# ESP-32-UNICLOCK-VFD.net
KiCad netlist of a schematic drawn in EAGLE
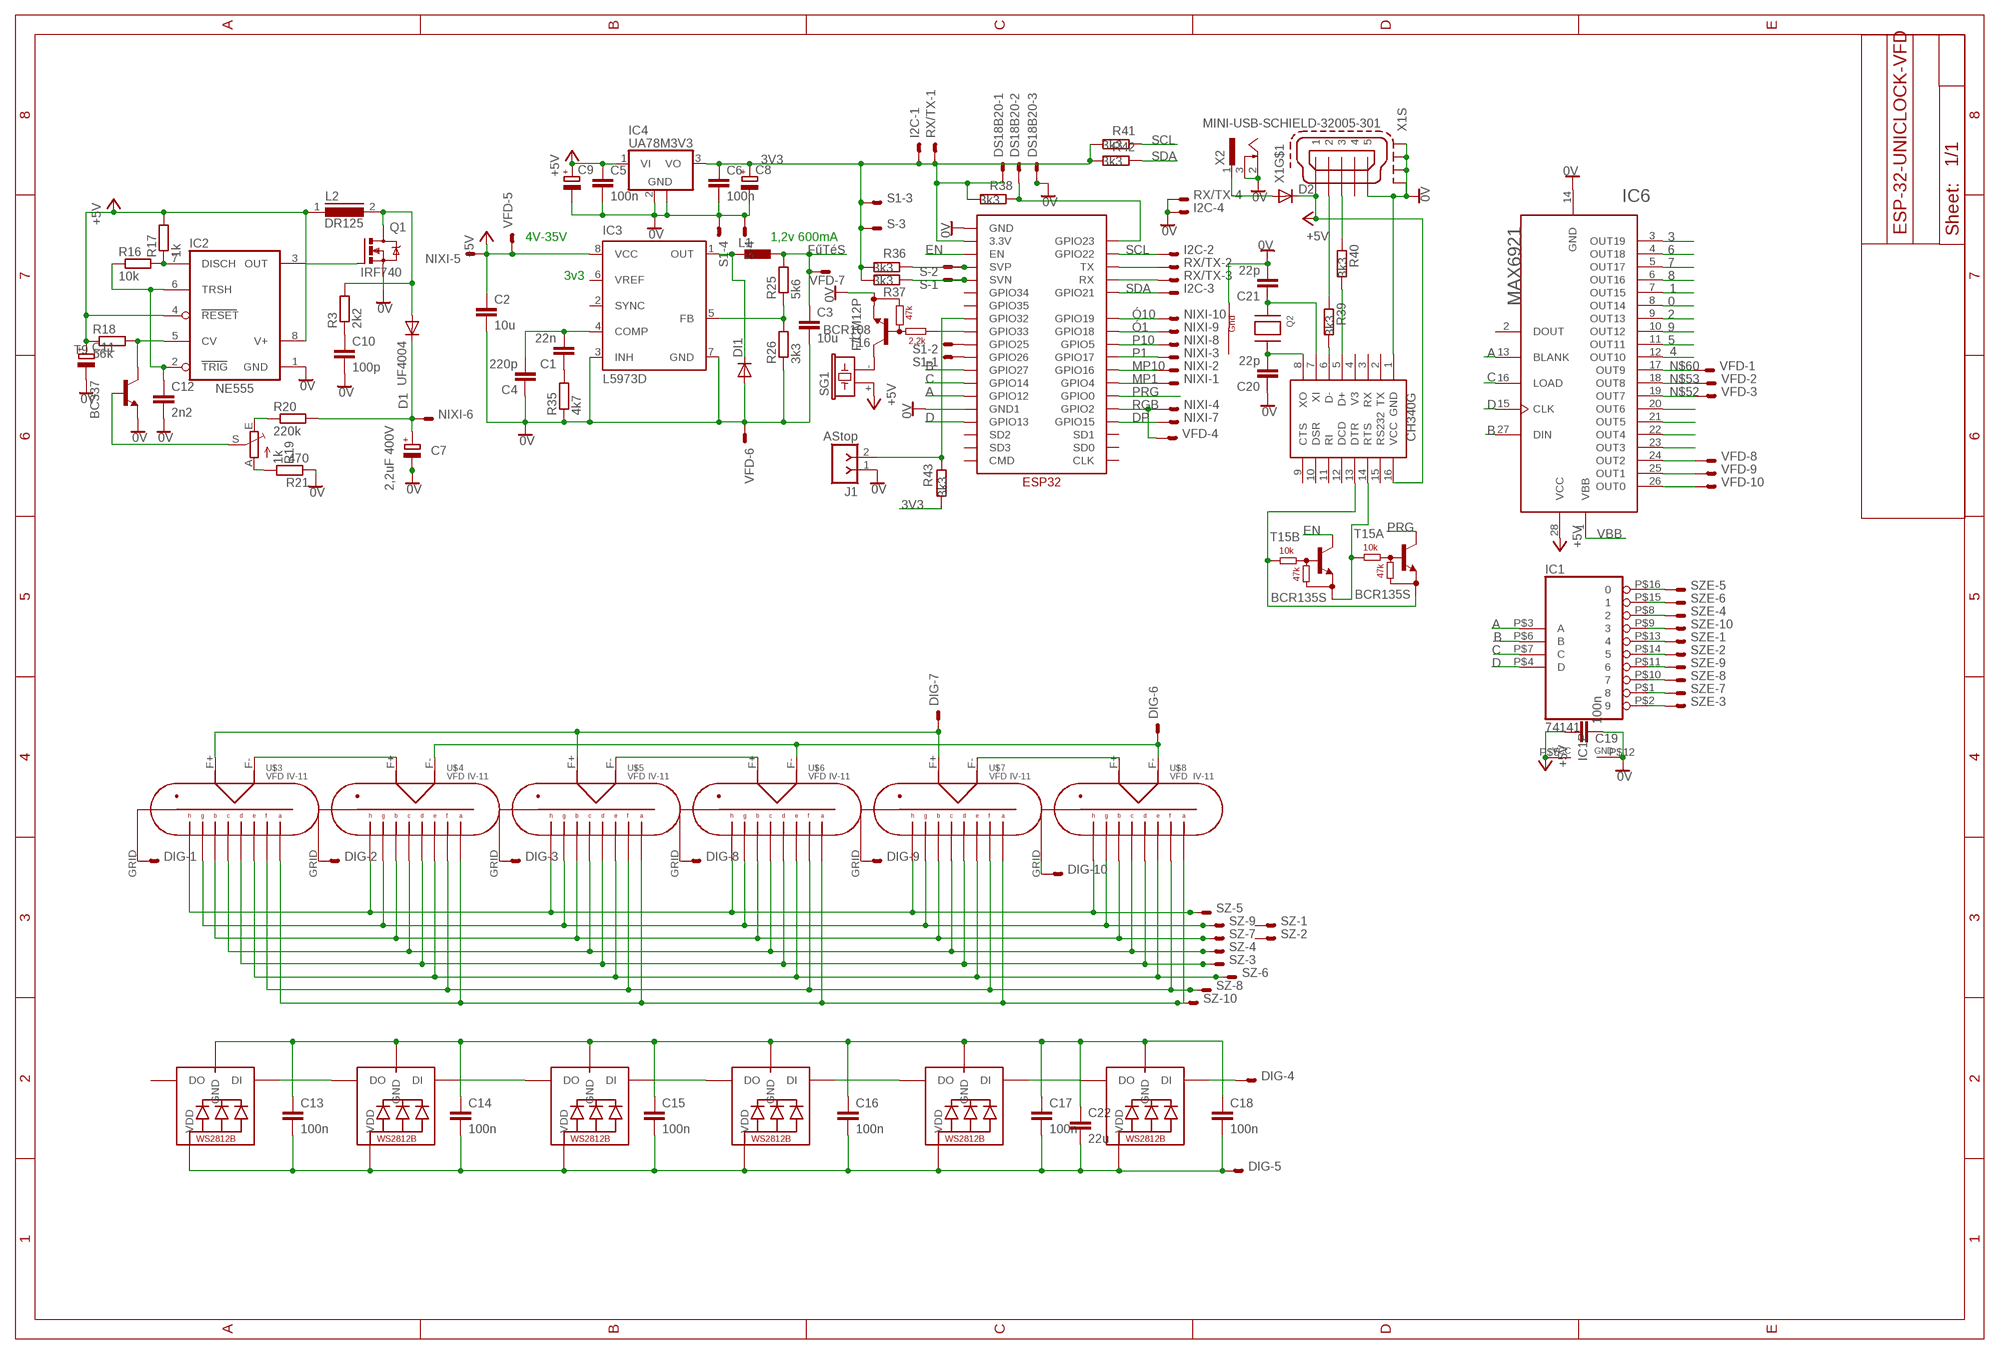
[diagram p0: schematic, sheet 1]

(export (version "E")
  (design (tool "Eeschema 10.0.6"))
  (components
    (comp (ref "C1")
      (value "22n")
      (footprint "eagle-import:0603")
      (libsource (lib "eagle-import") (part "C0603"))
    )
    (comp (ref "C2")
      (value "10u")
      (footprint "eagle-import:1206")
      (libsource (lib "eagle-import") (part "C1206"))
    )
    (comp (ref "C3")
      (value "10u")
      (footprint "eagle-import:1206")
      (libsource (lib "eagle-import") (part "C1206"))
    )
    (comp (ref "C4")
      (value "220p")
      (footprint "eagle-import:0603")
      (libsource (lib "eagle-import") (part "C0603"))
    )
    (comp (ref "C5")
      (value "100n")
      (footprint "eagle-import:0603")
      (libsource (lib "eagle-import") (part "C0603"))
    )
    (comp (ref "C6")
      (value "100n")
      (footprint "eagle-import:0603")
      (libsource (lib "eagle-import") (part "C0603"))
    )
    (comp (ref "C7")
      (value "2,2uF 400V")
      (footprint "eagle-import:E2,5-7")
      (libsource (lib "eagle-import") (part "CPOL-EUE2.5-7"))
    )
    (comp (ref "C8")
      (value "CPOL-EUE2.5-5")
      (footprint "eagle-import:E2,5-5")
      (libsource (lib "eagle-import") (part "CPOL-EUE2.5-5"))
    )
    (comp (ref "C9")
      (value "CPOL-EUE2.5-5")
      (footprint "eagle-import:E2,5-5")
      (libsource (lib "eagle-import") (part "CPOL-EUE2.5-5"))
    )
    (comp (ref "C10")
      (value "100p")
      (footprint "eagle-import:C050-024X044")
      (libsource (lib "eagle-import") (part "C-EU050-024X044"))
    )
    (comp (ref "C11")
      (value "CPOL-EUE2.5-7")
      (footprint "eagle-import:E2,5-7")
      (libsource (lib "eagle-import") (part "CPOL-EUE2.5-7"))
    )
    (comp (ref "C12")
      (value "2n2")
      (footprint "eagle-import:C0603")
      (libsource (lib "eagle-import") (part "C-EUC0603"))
    )
    (comp (ref "C13")
      (value "100n")
      (footprint "eagle-import:C0603")
      (libsource (lib "eagle-import") (part "C-EUC0603"))
    )
    (comp (ref "C14")
      (value "100n")
      (footprint "eagle-import:C0603")
      (libsource (lib "eagle-import") (part "C-EUC0603"))
    )
    (comp (ref "C15")
      (value "100n")
      (footprint "eagle-import:C0603")
      (libsource (lib "eagle-import") (part "C-EUC0603"))
    )
    (comp (ref "C16")
      (value "100n")
      (footprint "eagle-import:C0603")
      (libsource (lib "eagle-import") (part "C-EUC0603"))
    )
    (comp (ref "C17")
      (value "100n")
      (footprint "eagle-import:C0603")
      (libsource (lib "eagle-import") (part "C-EUC0603"))
    )
    (comp (ref "C18")
      (value "100n")
      (footprint "eagle-import:C0603")
      (libsource (lib "eagle-import") (part "C-EUC0603"))
    )
    (comp (ref "C19")
      (value "100n")
      (footprint "eagle-import:0603")
      (libsource (lib "eagle-import") (part "C0603"))
    )
    (comp (ref "C20")
      (value "22p")
      (footprint "eagle-import:0603")
      (libsource (lib "eagle-import") (part "C0603"))
    )
    (comp (ref "C21")
      (value "22p")
      (footprint "eagle-import:0603")
      (libsource (lib "eagle-import") (part "C0603"))
    )
    (comp (ref "C22")
      (value "22u")
      (footprint "eagle-import:C1206K")
      (libsource (lib "eagle-import") (part "C-EUC1206K"))
    )
    (comp (ref "D1")
      (value "UF4004")
      (footprint "eagle-import:DO35-10")
      (libsource (lib "eagle-import") (part "BA221"))
    )
    (comp (ref "D2")
      (value "DIODE-SOD123")
      (footprint "eagle-import:SOD123")
      (libsource (lib "eagle-import") (part "DIODE-SOD123"))
    )
    (comp (ref "DI1")
      (value "DDI214")
      (footprint "eagle-import:DI-214")
      (libsource (lib "eagle-import") (part "DDI214"))
    )
    (comp (ref "DIG")
      (value "DIG")
      (footprint "eagle-import:PAD10")
      (libsource (lib "eagle-import") (part "PAD10"))
    )
    (comp (ref "DS18B20")
      (value "PAD3")
      (footprint "eagle-import:PAD3")
      (libsource (lib "eagle-import") (part "PAD3"))
    )
    (comp (ref "I2C")
      (value "PAD4")
      (footprint "eagle-import:PAD4")
      (libsource (lib "eagle-import") (part "PAD4"))
    )
    (comp (ref "IC1")
      (value "74141")
      (footprint "eagle-import:DIL16SMD")
      (libsource (lib "eagle-import") (part "74141"))
    )
    (comp (ref "IC2")
      (value "NE555")
      (footprint "eagle-import:DIL08")
      (fields (field (name "MF") "MAXIM") (field (name "MPN") "ICM7555IPA+"))
      (libsource (lib "eagle-import") (part "ICM7555"))
    )
    (comp (ref "IC3")
      (value "L5973D")
      (footprint "eagle-import:HSOP8")
      (fields (field (name "MF") "STMICROELECTRONICS"))
      (libsource (lib "eagle-import") (part "L5973D"))
    )
    (comp (ref "IC4")
      (value "UA78M3V3")
      (footprint "eagle-import:SOT223")
      (libsource (lib "eagle-import") (part "UA78MDCY05"))
    )
    (comp (ref "IC6")
      (value "MAX6921")
      (footprint "eagle-import:SO-28W")
      (libsource (lib "eagle-import") (part "MAX6921SOIC28W"))
    )
    (comp (ref "J1")
      (value "AStop")
      (footprint "eagle-import:SIP-100-02-32")
      (libsource (lib "eagle-import") (part "F-1X02-SIP-100-32"))
    )
    (comp (ref "L1")
      (value "LDR73A")
      (footprint "eagle-import:DR73A")
      (libsource (lib "eagle-import") (part "LDR73A"))
    )
    (comp (ref "L2")
      (value "DR125")
      (footprint "eagle-import:DR125")
      (libsource (lib "eagle-import") (part "DR125"))
    )
    (comp (ref "LED1")
      (value "WS2812B_5050N")
      (footprint "eagle-import:WS2812B-NARROW")
      (libsource (lib "eagle-import") (part "WS2812B_5050N"))
    )
    (comp (ref "LED2")
      (value "WS2812B_5050N")
      (footprint "eagle-import:WS2812B-NARROW")
      (libsource (lib "eagle-import") (part "WS2812B_5050N"))
    )
    (comp (ref "LED3")
      (value "WS2812B_5050N")
      (footprint "eagle-import:WS2812B-NARROW")
      (libsource (lib "eagle-import") (part "WS2812B_5050N"))
    )
    (comp (ref "LED4")
      (value "WS2812B_5050N")
      (footprint "eagle-import:WS2812B-NARROW")
      (libsource (lib "eagle-import") (part "WS2812B_5050N"))
    )
    (comp (ref "LED5")
      (value "WS2812B_5050N")
      (footprint "eagle-import:WS2812B-NARROW")
      (libsource (lib "eagle-import") (part "WS2812B_5050N"))
    )
    (comp (ref "LED6")
      (value "WS2812B_5050N")
      (footprint "eagle-import:WS2812B-NARROW")
      (libsource (lib "eagle-import") (part "WS2812B_5050N"))
    )
    (comp (ref "NIXI")
      (value "PAD10")
      (footprint "eagle-import:PAD10")
      (libsource (lib "eagle-import") (part "PAD10"))
    )
    (comp (ref "Q1")
      (value "IRF740")
      (footprint "eagle-import:TO220BV")
      (libsource (lib "eagle-import") (part "IRF740"))
    )
    (comp (ref "Q2")
      (value "XTAL-4-3225")
      (footprint "eagle-import:NX3225")
      (libsource (lib "eagle-import") (part "XTAL-4-3225"))
    )
    (comp (ref "R3")
      (value "2k2")
      (footprint "eagle-import:0204_7")
      (libsource (lib "eagle-import") (part "R-EU_0204/7"))
    )
    (comp (ref "R16")
      (value "10k")
      (footprint "eagle-import:R0603")
      (libsource (lib "eagle-import") (part "R-EU_R0603"))
    )
    (comp (ref "R17")
      (value "1k")
      (footprint "eagle-import:R0603")
      (libsource (lib "eagle-import") (part "R-EU_R0603"))
    )
    (comp (ref "R18")
      (value "56k")
      (footprint "eagle-import:R0603")
      (libsource (lib "eagle-import") (part "R-EU_R0603"))
    )
    (comp (ref "R19")
      (value "1k")
      (footprint "eagle-import:CA6H")
      (libsource (lib "eagle-import") (part "TRIM_EU-CA6H"))
    )
    (comp (ref "R20")
      (value "220k")
      (footprint "eagle-import:0204_7")
      (libsource (lib "eagle-import") (part "R-EU_0204/7"))
    )
    (comp (ref "R21")
      (value "470")
      (footprint "eagle-import:0204_7")
      (libsource (lib "eagle-import") (part "R-EU_0204/7"))
    )
    (comp (ref "R25")
      (value "5k6")
      (footprint "eagle-import:0603")
      (libsource (lib "eagle-import") (part "R0603"))
    )
    (comp (ref "R26")
      (value "3k3")
      (footprint "eagle-import:0603")
      (libsource (lib "eagle-import") (part "R0603"))
    )
    (comp (ref "R35")
      (value "4k7")
      (footprint "eagle-import:0603")
      (libsource (lib "eagle-import") (part "R0603"))
    )
    (comp (ref "R36")
      (value "3k3")
      (footprint "eagle-import:0603")
      (libsource (lib "eagle-import") (part "R0603"))
    )
    (comp (ref "R37")
      (value "3k3")
      (footprint "eagle-import:0603")
      (libsource (lib "eagle-import") (part "R0603"))
    )
    (comp (ref "R38")
      (value "3k3")
      (footprint "eagle-import:0603")
      (libsource (lib "eagle-import") (part "R0603"))
    )
    (comp (ref "R39")
      (value "3k3")
      (footprint "eagle-import:0603")
      (libsource (lib "eagle-import") (part "R0603"))
    )
    (comp (ref "R40")
      (value "3k3")
      (footprint "eagle-import:0603")
      (libsource (lib "eagle-import") (part "R0603"))
    )
    (comp (ref "R41")
      (value "3k3")
      (footprint "eagle-import:0603")
      (libsource (lib "eagle-import") (part "R0603"))
    )
    (comp (ref "R42")
      (value "3k3")
      (footprint "eagle-import:0603")
      (libsource (lib "eagle-import") (part "R0603"))
    )
    (comp (ref "R43")
      (value "3k3")
      (footprint "eagle-import:0603")
      (libsource (lib "eagle-import") (part "R0603"))
    )
    (comp (ref "RX/TX")
      (value "PAD4")
      (footprint "eagle-import:PAD4")
      (libsource (lib "eagle-import") (part "PAD4"))
    )
    (comp (ref "S")
      (value "PAD4")
      (footprint "eagle-import:PAD4")
      (libsource (lib "eagle-import") (part "PAD4"))
    )
    (comp (ref "S1")
      (value "PAD4")
      (footprint "eagle-import:PAD4")
      (libsource (lib "eagle-import") (part "PAD4"))
    )
    (comp (ref "SG1")
      (value "F/CM12P")
      (footprint "eagle-import:F_CM12P")
      (libsource (lib "eagle-import") (part "F/CM12P"))
    )
    (comp (ref "SZ")
      (value "PAD10")
      (footprint "eagle-import:PAD10")
      (libsource (lib "eagle-import") (part "PAD10"))
    )
    (comp (ref "SZE")
      (value "PAD10")
      (footprint "eagle-import:PAD10")
      (libsource (lib "eagle-import") (part "PAD10"))
    )
    (comp (ref "T9")
      (value "BC337")
      (footprint "eagle-import:TO92-CBE")
      (libsource (lib "eagle-import") (part "-NPN-TO92-CBEBC237"))
    )
    (comp (ref "T15")
      (value "BCR135S")
      (footprint "eagle-import:SOT363_INFINEON")
      (libsource (lib "eagle-import") (part "BCR135S"))
    )
    (comp (ref "T16")
      (value "BCR108")
      (footprint "eagle-import:SOT23-BEC")
      (libsource (lib "eagle-import") (part "BCR108"))
    )
    (comp (ref "U$1")
      (value "CH340G")
      (footprint "eagle-import:SOIC16")
      (libsource (lib "eagle-import") (part "CH340G"))
    )
    (comp (ref "U$2")
      (value "ESP32-2X18")
      (footprint "eagle-import:ESP322X18")
      (libsource (lib "eagle-import") (part "ESP32-2X18"))
    )
    (comp (ref "U$3")
      (value "VFD IV-11")
      (footprint "eagle-import:VFD-IV_11-ZOLI")
      (libsource (lib "eagle-import") (part "VFD-IV-11-ZOLI"))
    )
    (comp (ref "U$4")
      (value "VFD IV-11")
      (footprint "eagle-import:VFD-IV_11-ZOLI")
      (libsource (lib "eagle-import") (part "VFD-IV-11-ZOLI"))
    )
    (comp (ref "U$5")
      (value "VFD IV-11")
      (footprint "eagle-import:VFD-IV_11-ZOLI")
      (libsource (lib "eagle-import") (part "VFD-IV-11-ZOLI"))
    )
    (comp (ref "U$6")
      (value "VFD IV-11")
      (footprint "eagle-import:VFD-IV_11-ZOLI")
      (libsource (lib "eagle-import") (part "VFD-IV-11-ZOLI"))
    )
    (comp (ref "U$7")
      (value "VFD IV-11")
      (footprint "eagle-import:VFD-IV_11-ZOLI")
      (libsource (lib "eagle-import") (part "VFD-IV-11-ZOLI"))
    )
    (comp (ref "U$8")
      (value "VFD IV-11")
      (footprint "eagle-import:VFD-IV_11-ZOLI")
      (libsource (lib "eagle-import") (part "VFD-IV-11-ZOLI"))
    )
    (comp (ref "VFD")
      (value "PAD10")
      (footprint "eagle-import:PAD10")
      (libsource (lib "eagle-import") (part "PAD10"))
    )
    (comp (ref "X1")
      (value "MINI-USB-SCHIELD-32005-301")
      (footprint "eagle-import:32005-301")
      (libsource (lib "eagle-import") (part "MINI-USB-SCHIELD-32005-301"))
    )
    (comp (ref "X2")
      (value "733989-5")
      (footprint "eagle-import:733989-5")
      (libsource (lib "eagle-import") (part "73398?9-5"))
    )
  )
  (nets
    (net (code "1") (name "+5V") (class "Default")
      (node (ref "C11") (pin "+") (pinfunction "+_+") (pintype "passive"))
      (node (ref "C19") (pin "1") (pinfunction "1_1") (pintype "passive"))
      (node (ref "C2") (pin "1") (pinfunction "1_1") (pintype "passive"))
      (node (ref "C5") (pin "1") (pinfunction "1_1") (pintype "passive"))
      (node (ref "C9") (pin "+") (pinfunction "+_+") (pintype "passive"))
      (node (ref "D2") (pin "C") (pinfunction "C_C") (pintype "passive"))
      (node (ref "IC1") (pin "P$5") (pinfunction "VCC_P$5") (pintype "power_in"))
      (node (ref "IC2") (pin "4") (pinfunction "RESET_4") (pintype "input"))
      (node (ref "IC2") (pin "8") (pinfunction "V+_8") (pintype "power_in"))
      (node (ref "IC3") (pin "8") (pinfunction "VCC_8") (pintype "input"))
      (node (ref "IC4") (pin "1") (pinfunction "VI_1") (pintype "input"))
      (node (ref "IC6") (pin "28") (pinfunction "VCC_28") (pintype "power_in"))
      (node (ref "L2") (pin "1") (pinfunction "1_1") (pintype "passive"))
      (node (ref "NIXI") (pin "P$5") (pinfunction "S_P$5") (pintype "passive"))
      (node (ref "R17") (pin "2") (pinfunction "2_2") (pintype "passive"))
      (node (ref "R18") (pin "1") (pinfunction "1_1") (pintype "passive"))
      (node (ref "SG1") (pin "+") (pinfunction "1_+") (pintype "passive"))
      (node (ref "U$1") (pin "16") (pinfunction "VCC_16") (pintype "bidirectional"))
      (node (ref "VFD") (pin "P$5") (pinfunction "S_P$5") (pintype "passive"))
      (node (ref "X1") (pin "1") (pinfunction "1_1") (pintype "passive"))
    )
    (net (code "2") (name "/0") (class "Default")
      (node (ref "IC1") (pin "P$16") (pinfunction "0_P$16") (pintype "open_collector"))
      (node (ref "IC6") (pin "8") (pinfunction "OUT14_8") (pintype "output"))
      (node (ref "SZE") (pin "P$5") (pinfunction "S_P$5") (pintype "passive"))
    )
    (net (code "3") (name "/1") (class "Default")
      (node (ref "IC1") (pin "P$15") (pinfunction "1_P$15") (pintype "open_collector"))
      (node (ref "IC6") (pin "7") (pinfunction "OUT15_7") (pintype "output"))
      (node (ref "SZE") (pin "P$6") (pinfunction "S_P$6") (pintype "passive"))
    )
    (net (code "4") (name "/2") (class "Default")
      (node (ref "IC1") (pin "P$8") (pinfunction "2_P$8") (pintype "open_collector"))
      (node (ref "IC6") (pin "9") (pinfunction "OUT13_9") (pintype "output"))
      (node (ref "SZE") (pin "P$4") (pinfunction "S_P$4") (pintype "passive"))
    )
    (net (code "5") (name "/3") (class "Default")
      (node (ref "IC1") (pin "P$9") (pinfunction "3_P$9") (pintype "open_collector"))
      (node (ref "IC6") (pin "3") (pinfunction "OUT19_3") (pintype "output"))
      (node (ref "SZE") (pin "P$10") (pinfunction "S_P$10") (pintype "passive"))
    )
    (net (code "6") (name "/3V3") (class "Default")
      (node (ref "C6") (pin "1") (pinfunction "1_1") (pintype "passive"))
      (node (ref "C8") (pin "+") (pinfunction "+_+") (pintype "passive"))
      (node (ref "DS18B20") (pin "P$1") (pinfunction "S_P$1") (pintype "passive"))
      (node (ref "I2C") (pin "P$1") (pinfunction "S_P$1") (pintype "passive"))
      (node (ref "IC4") (pin "3") (pinfunction "VO_3") (pintype "passive"))
      (node (ref "R36") (pin "2") (pinfunction "2_2") (pintype "passive"))
      (node (ref "R37") (pin "2") (pinfunction "2_2") (pintype "passive"))
      (node (ref "R38") (pin "2") (pinfunction "2_2") (pintype "passive"))
      (node (ref "R41") (pin "2") (pinfunction "2_2") (pintype "passive"))
      (node (ref "R42") (pin "2") (pinfunction "2_2") (pintype "passive"))
      (node (ref "R43") (pin "2") (pinfunction "2_2") (pintype "passive"))
      (node (ref "RX/TX") (pin "P$1") (pinfunction "S_P$1") (pintype "passive"))
      (node (ref "S") (pin "P$3") (pinfunction "S_P$3") (pintype "passive"))
      (node (ref "S1") (pin "P$3") (pinfunction "S_P$3") (pintype "passive"))
      (node (ref "U$2") (pin "P$20") (pinfunction "3.3V_P$20") (pintype "bidirectional"))
    )
    (net (code "7") (name "/4") (class "Default")
      (node (ref "IC1") (pin "P$13") (pinfunction "4_P$13") (pintype "open_collector"))
      (node (ref "IC6") (pin "12") (pinfunction "OUT10_12") (pintype "output"))
      (node (ref "SZE") (pin "P$1") (pinfunction "S_P$1") (pintype "passive"))
    )
    (net (code "8") (name "/5") (class "Default")
      (node (ref "IC1") (pin "P$14") (pinfunction "5_P$14") (pintype "open_collector"))
      (node (ref "IC6") (pin "11") (pinfunction "OUT11_11") (pintype "output"))
      (node (ref "SZE") (pin "P$2") (pinfunction "S_P$2") (pintype "passive"))
    )
    (net (code "9") (name "/6") (class "Default")
      (node (ref "IC1") (pin "P$11") (pinfunction "6_P$11") (pintype "open_collector"))
      (node (ref "IC6") (pin "4") (pinfunction "OUT18_4") (pintype "output"))
      (node (ref "SZE") (pin "P$9") (pinfunction "S_P$9") (pintype "passive"))
    )
    (net (code "10") (name "/7") (class "Default")
      (node (ref "IC1") (pin "P$10") (pinfunction "7_P$10") (pintype "open_collector"))
      (node (ref "IC6") (pin "5") (pinfunction "OUT17_5") (pintype "output"))
      (node (ref "SZE") (pin "P$8") (pinfunction "S_P$8") (pintype "passive"))
    )
    (net (code "11") (name "/8") (class "Default")
      (node (ref "IC1") (pin "P$1") (pinfunction "8_P$1") (pintype "open_collector"))
      (node (ref "IC6") (pin "6") (pinfunction "OUT16_6") (pintype "output"))
      (node (ref "SZE") (pin "P$7") (pinfunction "S_P$7") (pintype "passive"))
    )
    (net (code "12") (name "/9") (class "Default")
      (node (ref "IC1") (pin "P$2") (pinfunction "9_P$2") (pintype "open_collector"))
      (node (ref "IC6") (pin "10") (pinfunction "OUT12_10") (pintype "output"))
      (node (ref "SZE") (pin "P$3") (pinfunction "S_P$3") (pintype "passive"))
    )
    (net (code "13") (name "/A") (class "Default")
      (node (ref "IC1") (pin "P$3") (pinfunction "A_P$3") (pintype "input"))
      (node (ref "IC6") (pin "13") (pinfunction "BLANK_13") (pintype "input"))
      (node (ref "U$2") (pin "P$12") (pinfunction "GPIO12_P$12") (pintype "bidirectional"))
    )
    (net (code "14") (name "/B") (class "Default")
      (node (ref "IC1") (pin "P$6") (pinfunction "B_P$6") (pintype "input"))
      (node (ref "IC6") (pin "27") (pinfunction "DIN_27") (pintype "input"))
      (node (ref "U$2") (pin "P$10") (pinfunction "GPIO27_P$10") (pintype "bidirectional"))
    )
    (net (code "15") (name "/C") (class "Default")
      (node (ref "IC1") (pin "P$7") (pinfunction "C_P$7") (pintype "input"))
      (node (ref "IC6") (pin "16") (pinfunction "LOAD_16") (pintype "input"))
      (node (ref "U$2") (pin "P$9") (pinfunction "GPIO14_P$9") (pintype "bidirectional"))
    )
    (net (code "16") (name "/D") (class "Default")
      (node (ref "IC1") (pin "P$4") (pinfunction "D_P$4") (pintype "input"))
      (node (ref "IC6") (pin "15") (pinfunction "CLK_15") (pintype "input"))
      (node (ref "U$2") (pin "P$11") (pinfunction "GPIO13_P$11") (pintype "bidirectional"))
    )
    (net (code "17") (name "/DP") (class "Default")
      (node (ref "NIXI") (pin "P$7") (pinfunction "S_P$7") (pintype "passive"))
      (node (ref "U$2") (pin "P$35") (pinfunction "GPIO15_P$35") (pintype "bidirectional"))
    )
    (net (code "18") (name "/EN") (class "Default")
      (node (ref "T15") (pin "3") (pinfunction "C_3") (pintype "passive"))
      (node (ref "U$2") (pin "P$21") (pinfunction "EN_P$21") (pintype "bidirectional"))
    )
    (net (code "19") (name "/FűTéS") (class "Default")
      (node (ref "C3") (pin "1") (pinfunction "1_1") (pintype "passive"))
      (node (ref "L1") (pin "2") (pinfunction "2_2") (pintype "passive"))
      (node (ref "R25") (pin "2") (pinfunction "2_2") (pintype "passive"))
      (node (ref "VFD") (pin "P$7") (pinfunction "S_P$7") (pintype "passive"))
    )
    (net (code "20") (name "/G2") (class "Default")
      (node (ref "Q2") (pin "2") (pinfunction "G2_2") (pintype "power_in"))
    )
    (net (code "21") (name "/GND") (class "Default")
      (node (ref "C13") (pin "1") (pinfunction "1_1") (pintype "passive"))
      (node (ref "C14") (pin "1") (pinfunction "1_1") (pintype "passive"))
      (node (ref "C15") (pin "1") (pinfunction "1_1") (pintype "passive"))
      (node (ref "C16") (pin "1") (pinfunction "1_1") (pintype "passive"))
      (node (ref "C17") (pin "1") (pinfunction "1_1") (pintype "passive"))
      (node (ref "C18") (pin "1") (pinfunction "1_1") (pintype "passive"))
      (node (ref "C22") (pin "1") (pinfunction "1_1") (pintype "passive"))
      (node (ref "DIG") (pin "P$6") (pinfunction "S_P$6") (pintype "passive"))
      (node (ref "LED1") (pin "3-GND") (pinfunction "GND_3-GND") (pintype "power_in"))
      (node (ref "LED2") (pin "3-GND") (pinfunction "GND_3-GND") (pintype "power_in"))
      (node (ref "LED3") (pin "3-GND") (pinfunction "GND_3-GND") (pintype "power_in"))
      (node (ref "LED4") (pin "3-GND") (pinfunction "GND_3-GND") (pintype "power_in"))
      (node (ref "LED5") (pin "3-GND") (pinfunction "GND_3-GND") (pintype "power_in"))
      (node (ref "LED6") (pin "3-GND") (pinfunction "GND_3-GND") (pintype "power_in"))
      (node (ref "U$4") (pin "F-") (pinfunction "F-_F-") (pintype "passive"))
      (node (ref "U$6") (pin "F-") (pinfunction "F-_F-") (pintype "passive"))
      (node (ref "U$8") (pin "F-") (pinfunction "F-_F-") (pintype "passive"))
    )
    (net (code "22") (name "/MP1") (class "Default")
      (node (ref "NIXI") (pin "P$1") (pinfunction "S_P$1") (pintype "passive"))
      (node (ref "U$2") (pin "P$34") (pinfunction "GPIO4_P$34") (pintype "bidirectional"))
    )
    (net (code "23") (name "/MP10") (class "Default")
      (node (ref "NIXI") (pin "P$2") (pinfunction "S_P$2") (pintype "passive"))
      (node (ref "U$2") (pin "P$31") (pinfunction "GPIO16_P$31") (pintype "bidirectional"))
    )
    (net (code "24") (name "/N$52") (class "Default")
      (node (ref "IC6") (pin "19") (pinfunction "OUT7_19") (pintype "output"))
      (node (ref "VFD") (pin "P$3") (pinfunction "S_P$3") (pintype "passive"))
    )
    (net (code "25") (name "/N$53") (class "Default")
      (node (ref "IC6") (pin "18") (pinfunction "OUT8_18") (pintype "output"))
      (node (ref "VFD") (pin "P$2") (pinfunction "S_P$2") (pintype "passive"))
    )
    (net (code "26") (name "/N$60") (class "Default")
      (node (ref "IC6") (pin "17") (pinfunction "OUT9_17") (pintype "output"))
      (node (ref "VFD") (pin "P$1") (pinfunction "S_P$1") (pintype "passive"))
    )
    (net (code "27") (name "/P1") (class "Default")
      (node (ref "NIXI") (pin "P$3") (pinfunction "S_P$3") (pintype "passive"))
      (node (ref "U$2") (pin "P$32") (pinfunction "GPIO17_P$32") (pintype "bidirectional"))
    )
    (net (code "28") (name "/P10") (class "Default")
      (node (ref "NIXI") (pin "P$8") (pinfunction "S_P$8") (pintype "passive"))
      (node (ref "U$2") (pin "P$29") (pinfunction "GPIO5_P$29") (pintype "bidirectional"))
    )
    (net (code "29") (name "/PRG") (class "Default")
      (node (ref "T15") (pin "6") (pinfunction "C_6") (pintype "passive"))
      (node (ref "U$2") (pin "P$33") (pinfunction "GPIO0_P$33") (pintype "bidirectional"))
    )
    (net (code "30") (name "/RGB") (class "Default")
      (node (ref "NIXI") (pin "P$4") (pinfunction "S_P$4") (pintype "passive"))
      (node (ref "U$2") (pin "P$36") (pinfunction "GPIO2_P$36") (pintype "bidirectional"))
      (node (ref "VFD") (pin "P$4") (pinfunction "S_P$4") (pintype "passive"))
    )
    (net (code "31") (name "/SCL") (class "Default")
      (node (ref "I2C") (pin "P$2") (pinfunction "S_P$2") (pintype "passive"))
      (node (ref "R41") (pin "1") (pinfunction "1_1") (pintype "passive"))
      (node (ref "U$2") (pin "P$25") (pinfunction "GPIO22_P$25") (pintype "bidirectional"))
    )
    (net (code "32") (name "/SDA") (class "Default")
      (node (ref "I2C") (pin "P$3") (pinfunction "S_P$3") (pintype "passive"))
      (node (ref "R42") (pin "1") (pinfunction "1_1") (pintype "passive"))
      (node (ref "U$2") (pin "P$28") (pinfunction "GPIO21_P$28") (pintype "bidirectional"))
    )
    (net (code "33") (name "/VBB") (class "Default")
      (node (ref "C7") (pin "+") (pinfunction "+_+") (pintype "passive"))
      (node (ref "D1") (pin "C") (pinfunction "C_C") (pintype "passive"))
      (node (ref "IC6") (pin "1") (pinfunction "VBB_1") (pintype "power_in"))
      (node (ref "NIXI") (pin "P$6") (pinfunction "S_P$6") (pintype "passive"))
      (node (ref "R20") (pin "2") (pinfunction "2_2") (pintype "passive"))
    )
    (net (code "34") (name "/Ó1") (class "Default")
      (node (ref "NIXI") (pin "P$9") (pinfunction "S_P$9") (pintype "passive"))
      (node (ref "U$2") (pin "P$30") (pinfunction "GPIO18_P$30") (pintype "bidirectional"))
    )
    (net (code "35") (name "/Ó10") (class "Default")
      (node (ref "NIXI") (pin "P$10") (pinfunction "S_P$10") (pintype "passive"))
      (node (ref "U$2") (pin "P$27") (pinfunction "GPIO19_P$27") (pintype "bidirectional"))
    )
    (net (code "36") (name "0V") (class "Default")
      (node (ref "C10") (pin "2") (pinfunction "2_2") (pintype "passive"))
      (node (ref "C11") (pin "-") (pinfunction "-_-") (pintype "passive"))
      (node (ref "C12") (pin "2") (pinfunction "2_2") (pintype "passive"))
      (node (ref "C19") (pin "2") (pinfunction "2_2") (pintype "passive"))
      (node (ref "C2") (pin "2") (pinfunction "2_2") (pintype "passive"))
      (node (ref "C20") (pin "1") (pinfunction "1_1") (pintype "passive"))
      (node (ref "C21") (pin "2") (pinfunction "2_2") (pintype "passive"))
      (node (ref "C3") (pin "2") (pinfunction "2_2") (pintype "passive"))
      (node (ref "C4") (pin "1") (pinfunction "1_1") (pintype "passive"))
      (node (ref "C5") (pin "2") (pinfunction "2_2") (pintype "passive"))
      (node (ref "C6") (pin "2") (pinfunction "2_2") (pintype "passive"))
      (node (ref "C7") (pin "-") (pinfunction "-_-") (pintype "passive"))
      (node (ref "C8") (pin "-") (pinfunction "-_-") (pintype "passive"))
      (node (ref "C9") (pin "-") (pinfunction "-_-") (pintype "passive"))
      (node (ref "DI1") (pin "A") (pinfunction "A_A") (pintype "passive"))
      (node (ref "DS18B20") (pin "P$3") (pinfunction "S_P$3") (pintype "passive"))
      (node (ref "I2C") (pin "P$4") (pinfunction "S_P$4") (pintype "passive"))
      (node (ref "IC1") (pin "P$12") (pinfunction "GND_P$12") (pintype "power_in"))
      (node (ref "IC2") (pin "1") (pinfunction "GND_1") (pintype "power_in"))
      (node (ref "IC3") (pin "3") (pinfunction "INH_3") (pintype "input"))
      (node (ref "IC3") (pin "7") (pinfunction "GND_7") (pintype "power_in"))
      (node (ref "IC4") (pin "2") (pinfunction "GND_2") (pintype "passive"))
      (node (ref "IC4") (pin "4") (pinfunction "GND_4") (pintype "passive"))
      (node (ref "IC6") (pin "14") (pinfunction "GND_14") (pintype "power_in"))
      (node (ref "J1") (pin "1") (pinfunction "1_1") (pintype "passive"))
      (node (ref "Q1") (pin "S") (pinfunction "S_S") (pintype "passive"))
      (node (ref "Q2") (pin "4") (pinfunction "G1_4") (pintype "power_in"))
      (node (ref "R21") (pin "1") (pinfunction "1_1") (pintype "passive"))
      (node (ref "R26") (pin "1") (pinfunction "1_1") (pintype "passive"))
      (node (ref "R35") (pin "1") (pinfunction "1_1") (pintype "passive"))
      (node (ref "RX/TX") (pin "P$4") (pinfunction "S_P$4") (pintype "passive"))
      (node (ref "S") (pin "P$4") (pinfunction "S_P$4") (pintype "passive"))
      (node (ref "S1") (pin "P$4") (pinfunction "S_P$4") (pintype "passive"))
      (node (ref "T16") (pin "E") (pinfunction "E_E") (pintype "passive"))
      (node (ref "T9") (pin "E") (pinfunction "E_E") (pintype "passive"))
      (node (ref "U$1") (pin "1") (pinfunction "GND_1") (pintype "bidirectional"))
      (node (ref "U$2") (pin "P$19") (pinfunction "GND_P$19") (pintype "bidirectional"))
      (node (ref "U$2") (pin "P$26") (pinfunction "GND1_P$26") (pintype "bidirectional"))
      (node (ref "VFD") (pin "P$6") (pinfunction "S_P$6") (pintype "passive"))
      (node (ref "X1") (pin "5") (pinfunction "5_5") (pintype "passive"))
      (node (ref "X1") (pin "M1") (pinfunction "S1_M1") (pintype "passive"))
      (node (ref "X1") (pin "M2") (pinfunction "S2_M2") (pintype "passive"))
      (node (ref "X1") (pin "M3") (pinfunction "S3_M3") (pintype "passive"))
      (node (ref "X1") (pin "M4") (pinfunction "S4_M4") (pintype "passive"))
      (node (ref "X2") (pin "2") (pinfunction "2_2") (pintype "passive"))
      (node (ref "X2") (pin "3") (pinfunction "3_3") (pintype "passive"))
    )
    (net (code "37") (name "Net-(C1-Pad1)") (class "Default")
      (node (ref "C1") (pin "1") (pinfunction "1_1") (pintype "passive"))
      (node (ref "R35") (pin "2") (pinfunction "2_2") (pintype "passive"))
    )
    (net (code "38") (name "Net-(C10-Pad1)") (class "Default")
      (node (ref "C10") (pin "1") (pinfunction "1_1") (pintype "passive"))
      (node (ref "R3") (pin "1") (pinfunction "1_1") (pintype "passive"))
    )
    (net (code "39") (name "Net-(D1-PadA)") (class "Default")
      (node (ref "D1") (pin "A") (pinfunction "A_A") (pintype "passive"))
      (node (ref "L2") (pin "2") (pinfunction "2_2") (pintype "passive"))
      (node (ref "Q1") (pin "D") (pinfunction "D_D") (pintype "passive"))
      (node (ref "R3") (pin "2") (pinfunction "2_2") (pintype "passive"))
    )
    (net (code "40") (name "Net-(D2-PadA)") (class "Default")
      (node (ref "D2") (pin "A") (pinfunction "A_A") (pintype "passive"))
      (node (ref "X2") (pin "1") (pinfunction "1_1") (pintype "passive"))
    )
    (net (code "41") (name "Net-(DI1-C)") (class "Default")
      (node (ref "DI1") (pin "K") (pinfunction "C_K") (pintype "passive"))
      (node (ref "IC3") (pin "1") (pinfunction "OUT_1") (pintype "output"))
      (node (ref "L1") (pin "1") (pinfunction "1_1") (pintype "passive"))
    )
    (net (code "42") (name "Net-(DIGA-S)") (class "Default")
      (node (ref "DIG") (pin "P$1") (pinfunction "S_P$1") (pintype "passive"))
      (node (ref "U$3") (pin "GRID") (pinfunction "GRID_GRID") (pintype "passive"))
    )
    (net (code "43") (name "Net-(DIGB-S)") (class "Default")
      (node (ref "DIG") (pin "P$10") (pinfunction "S_P$10") (pintype "passive"))
      (node (ref "U$8") (pin "GRID") (pinfunction "GRID_GRID") (pintype "passive"))
    )
    (net (code "44") (name "Net-(DIGC-S)") (class "Default")
      (node (ref "DIG") (pin "P$2") (pinfunction "S_P$2") (pintype "passive"))
      (node (ref "U$4") (pin "GRID") (pinfunction "GRID_GRID") (pintype "passive"))
    )
    (net (code "45") (name "Net-(DIGD-S)") (class "Default")
      (node (ref "DIG") (pin "P$3") (pinfunction "S_P$3") (pintype "passive"))
      (node (ref "U$5") (pin "GRID") (pinfunction "GRID_GRID") (pintype "passive"))
    )
    (net (code "46") (name "Net-(DIGE-S)") (class "Default")
      (node (ref "DIG") (pin "P$4") (pinfunction "S_P$4") (pintype "passive"))
      (node (ref "LED1") (pin "4-DIN") (pinfunction "DI_4-DIN") (pintype "input"))
    )
    (net (code "47") (name "Net-(DIGF-S)") (class "Default")
      (node (ref "C13") (pin "2") (pinfunction "2_2") (pintype "passive"))
      (node (ref "C14") (pin "2") (pinfunction "2_2") (pintype "passive"))
      (node (ref "C15") (pin "2") (pinfunction "2_2") (pintype "passive"))
      (node (ref "C16") (pin "2") (pinfunction "2_2") (pintype "passive"))
      (node (ref "C17") (pin "2") (pinfunction "2_2") (pintype "passive"))
      (node (ref "C18") (pin "2") (pinfunction "2_2") (pintype "passive"))
      (node (ref "C22") (pin "2") (pinfunction "2_2") (pintype "passive"))
      (node (ref "DIG") (pin "P$5") (pinfunction "S_P$5") (pintype "passive"))
      (node (ref "LED1") (pin "1-VDD") (pinfunction "VDD_1-VDD") (pintype "power_in"))
      (node (ref "LED2") (pin "1-VDD") (pinfunction "VDD_1-VDD") (pintype "power_in"))
      (node (ref "LED3") (pin "1-VDD") (pinfunction "VDD_1-VDD") (pintype "power_in"))
      (node (ref "LED4") (pin "1-VDD") (pinfunction "VDD_1-VDD") (pintype "power_in"))
      (node (ref "LED5") (pin "1-VDD") (pinfunction "VDD_1-VDD") (pintype "power_in"))
      (node (ref "LED6") (pin "1-VDD") (pinfunction "VDD_1-VDD") (pintype "power_in"))
    )
    (net (code "48") (name "Net-(DIGH-S)") (class "Default")
      (node (ref "DIG") (pin "P$7") (pinfunction "S_P$7") (pintype "passive"))
      (node (ref "U$3") (pin "F+") (pinfunction "F+_F+") (pintype "passive"))
      (node (ref "U$5") (pin "F+") (pinfunction "F+_F+") (pintype "passive"))
      (node (ref "U$7") (pin "F+") (pinfunction "F+_F+") (pintype "passive"))
    )
    (net (code "49") (name "Net-(DIGI-S)") (class "Default")
      (node (ref "DIG") (pin "P$8") (pinfunction "S_P$8") (pintype "passive"))
      (node (ref "U$6") (pin "GRID") (pinfunction "GRID_GRID") (pintype "passive"))
    )
    (net (code "50") (name "Net-(DIGJ-S)") (class "Default")
      (node (ref "DIG") (pin "P$9") (pinfunction "S_P$9") (pintype "passive"))
      (node (ref "U$7") (pin "GRID") (pinfunction "GRID_GRID") (pintype "passive"))
    )
    (net (code "51") (name "Net-(DS18B20B-S)") (class "Default")
      (node (ref "DS18B20") (pin "P$2") (pinfunction "S_P$2") (pintype "passive"))
      (node (ref "R38") (pin "1") (pinfunction "1_1") (pintype "passive"))
      (node (ref "U$2") (pin "P$23") (pinfunction "GPIO23_P$23") (pintype "bidirectional"))
    )
    (net (code "52") (name "Net-(IC2-CV)") (class "Default")
      (node (ref "IC2") (pin "5") (pinfunction "CV_5") (pintype "passive"))
      (node (ref "R18") (pin "2") (pinfunction "2_2") (pintype "passive"))
      (node (ref "T9") (pin "C") (pinfunction "C_C") (pintype "passive"))
    )
    (net (code "53") (name "Net-(IC2-DISCH)") (class "Default")
      (node (ref "IC2") (pin "7") (pinfunction "DISCH_7") (pintype "input"))
      (node (ref "R16") (pin "2") (pinfunction "2_2") (pintype "passive"))
      (node (ref "R17") (pin "1") (pinfunction "1_1") (pintype "passive"))
    )
    (net (code "54") (name "Net-(IC2-OUT)") (class "Default")
      (node (ref "IC2") (pin "3") (pinfunction "OUT_3") (pintype "output"))
      (node (ref "Q1") (pin "G") (pinfunction "G_G") (pintype "passive"))
    )
    (net (code "55") (name "Net-(IC2-TRIG)") (class "Default")
      (node (ref "C12") (pin "1") (pinfunction "1_1") (pintype "passive"))
      (node (ref "IC2") (pin "2") (pinfunction "TRIG_2") (pintype "bidirectional"))
      (node (ref "IC2") (pin "6") (pinfunction "TRSH_6") (pintype "input"))
      (node (ref "R16") (pin "1") (pinfunction "1_1") (pintype "passive"))
    )
    (net (code "56") (name "Net-(IC3B-COMP)") (class "Default")
      (node (ref "C1") (pin "2") (pinfunction "2_2") (pintype "passive"))
      (node (ref "C4") (pin "2") (pinfunction "2_2") (pintype "passive"))
      (node (ref "IC3") (pin "4") (pinfunction "COMP_4") (pintype "passive"))
    )
    (net (code "57") (name "Net-(IC3B-FB)") (class "Default")
      (node (ref "IC3") (pin "5") (pinfunction "FB_5") (pintype "input"))
      (node (ref "R25") (pin "1") (pinfunction "1_1") (pintype "passive"))
      (node (ref "R26") (pin "2") (pinfunction "2_2") (pintype "passive"))
    )
    (net (code "58") (name "Net-(IC6-OUT0)") (class "Default")
      (node (ref "IC6") (pin "26") (pinfunction "OUT0_26") (pintype "output"))
      (node (ref "VFD") (pin "P$10") (pinfunction "S_P$10") (pintype "passive"))
    )
    (net (code "59") (name "Net-(IC6-OUT1)") (class "Default")
      (node (ref "IC6") (pin "25") (pinfunction "OUT1_25") (pintype "output"))
      (node (ref "VFD") (pin "P$9") (pinfunction "S_P$9") (pintype "passive"))
    )
    (net (code "60") (name "Net-(IC6-OUT2)") (class "Default")
      (node (ref "IC6") (pin "24") (pinfunction "OUT2_24") (pintype "output"))
      (node (ref "VFD") (pin "P$8") (pinfunction "S_P$8") (pintype "passive"))
    )
    (net (code "61") (name "Net-(LED1-DO)") (class "Default")
      (node (ref "LED1") (pin "2-DOUT") (pinfunction "DO_2-DOUT") (pintype "output"))
      (node (ref "LED2") (pin "4-DIN") (pinfunction "DI_4-DIN") (pintype "input"))
    )
    (net (code "62") (name "Net-(LED2-DO)") (class "Default")
      (node (ref "LED2") (pin "2-DOUT") (pinfunction "DO_2-DOUT") (pintype "output"))
      (node (ref "LED3") (pin "4-DIN") (pinfunction "DI_4-DIN") (pintype "input"))
    )
    (net (code "63") (name "Net-(LED3-DO)") (class "Default")
      (node (ref "LED3") (pin "2-DOUT") (pinfunction "DO_2-DOUT") (pintype "output"))
      (node (ref "LED4") (pin "4-DIN") (pinfunction "DI_4-DIN") (pintype "input"))
    )
    (net (code "64") (name "Net-(LED4-DO)") (class "Default")
      (node (ref "LED4") (pin "2-DOUT") (pinfunction "DO_2-DOUT") (pintype "output"))
      (node (ref "LED5") (pin "4-DIN") (pinfunction "DI_4-DIN") (pintype "input"))
    )
    (net (code "65") (name "Net-(LED5-DO)") (class "Default")
      (node (ref "LED5") (pin "2-DOUT") (pinfunction "DO_2-DOUT") (pintype "output"))
      (node (ref "LED6") (pin "4-DIN") (pinfunction "DI_4-DIN") (pintype "input"))
    )
    (net (code "66") (name "Net-(Q2-X1)") (class "Default")
      (node (ref "C21") (pin "1") (pinfunction "1_1") (pintype "passive"))
      (node (ref "Q2") (pin "1") (pinfunction "X1_1") (pintype "bidirectional"))
      (node (ref "U$1") (pin "7") (pinfunction "XI_7") (pintype "bidirectional"))
    )
    (net (code "67") (name "Net-(Q2-X2)") (class "Default")
      (node (ref "C20") (pin "2") (pinfunction "2_2") (pintype "passive"))
      (node (ref "Q2") (pin "3") (pinfunction "X2_3") (pintype "bidirectional"))
      (node (ref "U$1") (pin "8") (pinfunction "XO_8") (pintype "bidirectional"))
    )
    (net (code "68") (name "Net-(R19-PadA)") (class "Default")
      (node (ref "R19") (pin "A") (pinfunction "A_A") (pintype "passive"))
      (node (ref "R21") (pin "2") (pinfunction "2_2") (pintype "passive"))
    )
    (net (code "69") (name "Net-(R19-PadE)") (class "Default")
      (node (ref "R19") (pin "E") (pinfunction "E_E") (pintype "passive"))
      (node (ref "R20") (pin "1") (pinfunction "1_1") (pintype "passive"))
    )
    (net (code "70") (name "Net-(R19-PadS)") (class "Default")
      (node (ref "R19") (pin "S") (pinfunction "S_S") (pintype "passive"))
      (node (ref "T9") (pin "B") (pinfunction "B_B") (pintype "passive"))
    )
    (net (code "71") (name "Net-(R39-Pad1)") (class "Default")
      (node (ref "R39") (pin "1") (pinfunction "1_1") (pintype "passive"))
      (node (ref "X1") (pin "2") (pinfunction "2_2") (pintype "passive"))
    )
    (net (code "72") (name "Net-(R40-Pad1)") (class "Default")
      (node (ref "R40") (pin "1") (pinfunction "1_1") (pintype "passive"))
      (node (ref "X1") (pin "3") (pinfunction "3_3") (pintype "passive"))
    )
    (net (code "73") (name "Net-(RX/TXB-S)") (class "Default")
      (node (ref "RX/TX") (pin "P$2") (pinfunction "S_P$2") (pintype "passive"))
      (node (ref "U$2") (pin "P$22") (pinfunction "TX_P$22") (pintype "bidirectional"))
    )
    (net (code "74") (name "Net-(RX/TXC-S)") (class "Default")
      (node (ref "RX/TX") (pin "P$3") (pinfunction "S_P$3") (pintype "passive"))
      (node (ref "U$2") (pin "P$24") (pinfunction "RX_P$24") (pintype "bidirectional"))
    )
    (net (code "75") (name "Net-(S1A-S)") (class "Default")
      (node (ref "S1") (pin "P$1") (pinfunction "S_P$1") (pintype "passive"))
      (node (ref "U$2") (pin "P$7") (pinfunction "GPIO26_P$7") (pintype "bidirectional"))
    )
    (net (code "76") (name "Net-(S1B-S)") (class "Default")
      (node (ref "S1") (pin "P$2") (pinfunction "S_P$2") (pintype "passive"))
      (node (ref "U$2") (pin "P$8") (pinfunction "GPIO25_P$8") (pintype "bidirectional"))
    )
    (net (code "77") (name "Net-(SA-S)") (class "Default")
      (node (ref "R37") (pin "1") (pinfunction "1_1") (pintype "passive"))
      (node (ref "S") (pin "P$1") (pinfunction "S_P$1") (pintype "passive"))
      (node (ref "U$2") (pin "P$1") (pinfunction "SVN_P$1") (pintype "bidirectional"))
    )
    (net (code "78") (name "Net-(SB-S)") (class "Default")
      (node (ref "R36") (pin "1") (pinfunction "1_1") (pintype "passive"))
      (node (ref "S") (pin "P$2") (pinfunction "S_P$2") (pintype "passive"))
      (node (ref "U$2") (pin "P$2") (pinfunction "SVP_P$2") (pintype "bidirectional"))
    )
    (net (code "79") (name "Net-(SG1-2)") (class "Default")
      (node (ref "SG1") (pin "-") (pinfunction "2_-") (pintype "passive"))
      (node (ref "T16") (pin "C") (pinfunction "C_C") (pintype "passive"))
    )
    (net (code "80") (name "Net-(SZB-S)") (class "Default")
      (node (ref "SZ") (pin "P$10") (pinfunction "S_P$10") (pintype "passive"))
      (node (ref "U$3") (pin "A") (pinfunction "P$1_A") (pintype "passive"))
      (node (ref "U$4") (pin "A") (pinfunction "P$1_A") (pintype "passive"))
      (node (ref "U$5") (pin "A") (pinfunction "P$1_A") (pintype "passive"))
      (node (ref "U$6") (pin "A") (pinfunction "P$1_A") (pintype "passive"))
      (node (ref "U$7") (pin "A") (pinfunction "P$1_A") (pintype "passive"))
      (node (ref "U$8") (pin "A") (pinfunction "P$1_A") (pintype "passive"))
    )
    (net (code "81") (name "Net-(SZD-S)") (class "Default")
      (node (ref "SZ") (pin "P$3") (pinfunction "S_P$3") (pintype "passive"))
      (node (ref "U$3") (pin "D") (pinfunction "P$4_D") (pintype "passive"))
      (node (ref "U$4") (pin "D") (pinfunction "P$4_D") (pintype "passive"))
      (node (ref "U$5") (pin "D") (pinfunction "P$4_D") (pintype "passive"))
      (node (ref "U$6") (pin "D") (pinfunction "P$4_D") (pintype "passive"))
      (node (ref "U$7") (pin "D") (pinfunction "P$4_D") (pintype "passive"))
      (node (ref "U$8") (pin "D") (pinfunction "P$4_D") (pintype "passive"))
    )
    (net (code "82") (name "Net-(SZE-S)") (class "Default")
      (node (ref "SZ") (pin "P$4") (pinfunction "S_P$4") (pintype "passive"))
      (node (ref "U$3") (pin "C") (pinfunction "P$5_C") (pintype "passive"))
      (node (ref "U$4") (pin "C") (pinfunction "P$5_C") (pintype "passive"))
      (node (ref "U$5") (pin "C") (pinfunction "P$5_C") (pintype "passive"))
      (node (ref "U$6") (pin "C") (pinfunction "P$5_C") (pintype "passive"))
      (node (ref "U$7") (pin "C") (pinfunction "P$5_C") (pintype "passive"))
      (node (ref "U$8") (pin "C") (pinfunction "P$5_C") (pintype "passive"))
    )
    (net (code "83") (name "Net-(SZF-S)") (class "Default")
      (node (ref "SZ") (pin "P$5") (pinfunction "S_P$5") (pintype "passive"))
      (node (ref "U$3") (pin "H") (pinfunction "P$8_H") (pintype "passive"))
      (node (ref "U$4") (pin "H") (pinfunction "P$8_H") (pintype "passive"))
      (node (ref "U$5") (pin "H") (pinfunction "P$8_H") (pintype "passive"))
      (node (ref "U$6") (pin "H") (pinfunction "P$8_H") (pintype "passive"))
      (node (ref "U$7") (pin "H") (pinfunction "P$8_H") (pintype "passive"))
      (node (ref "U$8") (pin "H") (pinfunction "P$8_H") (pintype "passive"))
    )
    (net (code "84") (name "Net-(SZG-S)") (class "Default")
      (node (ref "SZ") (pin "P$6") (pinfunction "S_P$6") (pintype "passive"))
      (node (ref "U$3") (pin "E") (pinfunction "P$3_E") (pintype "passive"))
      (node (ref "U$4") (pin "E") (pinfunction "P$3_E") (pintype "passive"))
      (node (ref "U$5") (pin "E") (pinfunction "P$3_E") (pintype "passive"))
      (node (ref "U$6") (pin "E") (pinfunction "P$3_E") (pintype "passive"))
      (node (ref "U$7") (pin "E") (pinfunction "P$3_E") (pintype "passive"))
      (node (ref "U$8") (pin "E") (pinfunction "P$3_E") (pintype "passive"))
    )
    (net (code "85") (name "Net-(SZH-S)") (class "Default")
      (node (ref "SZ") (pin "P$7") (pinfunction "S_P$7") (pintype "passive"))
      (node (ref "U$3") (pin "B") (pinfunction "P$6_B") (pintype "passive"))
      (node (ref "U$4") (pin "B") (pinfunction "P$6_B") (pintype "passive"))
      (node (ref "U$5") (pin "B") (pinfunction "P$6_B") (pintype "passive"))
      (node (ref "U$6") (pin "B") (pinfunction "P$6_B") (pintype "passive"))
      (node (ref "U$7") (pin "B") (pinfunction "P$6_B") (pintype "passive"))
      (node (ref "U$8") (pin "B") (pinfunction "P$6_B") (pintype "passive"))
    )
    (net (code "86") (name "Net-(SZI-S)") (class "Default")
      (node (ref "SZ") (pin "P$8") (pinfunction "S_P$8") (pintype "passive"))
      (node (ref "U$3") (pin "F") (pinfunction "P$2_F") (pintype "passive"))
      (node (ref "U$4") (pin "F") (pinfunction "P$2_F") (pintype "passive"))
      (node (ref "U$5") (pin "F") (pinfunction "P$2_F") (pintype "passive"))
      (node (ref "U$6") (pin "F") (pinfunction "P$2_F") (pintype "passive"))
      (node (ref "U$7") (pin "F") (pinfunction "P$2_F") (pintype "passive"))
      (node (ref "U$8") (pin "F") (pinfunction "P$2_F") (pintype "passive"))
    )
    (net (code "87") (name "Net-(SZJ-S)") (class "Default")
      (node (ref "SZ") (pin "P$9") (pinfunction "S_P$9") (pintype "passive"))
      (node (ref "U$3") (pin "G") (pinfunction "P$7_G") (pintype "passive"))
      (node (ref "U$4") (pin "G") (pinfunction "P$7_G") (pintype "passive"))
      (node (ref "U$5") (pin "G") (pinfunction "P$7_G") (pintype "passive"))
      (node (ref "U$6") (pin "G") (pinfunction "P$7_G") (pintype "passive"))
      (node (ref "U$7") (pin "G") (pinfunction "P$7_G") (pintype "passive"))
      (node (ref "U$8") (pin "G") (pinfunction "P$7_G") (pintype "passive"))
    )
    (net (code "88") (name "Net-(T15A-B)") (class "Default")
      (node (ref "T15") (pin "2") (pinfunction "B_2") (pintype "passive"))
      (node (ref "T15") (pin "4") (pinfunction "E_4") (pintype "passive"))
      (node (ref "U$1") (pin "14") (pinfunction "RTS_14") (pintype "bidirectional"))
    )
    (net (code "89") (name "Net-(T15A-E)") (class "Default")
      (node (ref "T15") (pin "1") (pinfunction "E_1") (pintype "passive"))
      (node (ref "T15") (pin "5") (pinfunction "B_5") (pintype "passive"))
      (node (ref "U$1") (pin "13") (pinfunction "DTR_13") (pintype "bidirectional"))
    )
    (net (code "90") (name "Net-(U$1-D+)") (class "Default")
      (node (ref "R40") (pin "2") (pinfunction "2_2") (pintype "passive"))
      (node (ref "U$1") (pin "5") (pinfunction "D+_5") (pintype "bidirectional"))
    )
    (net (code "91") (name "Net-(U$1-D-)") (class "Default")
      (node (ref "R39") (pin "2") (pinfunction "2_2") (pintype "passive"))
      (node (ref "U$1") (pin "6") (pinfunction "D-_6") (pintype "bidirectional"))
    )
    (net (code "92") (name "Net-(U$2-GPIO32)") (class "Default")
      (node (ref "J1") (pin "2") (pinfunction "2_2") (pintype "passive"))
      (node (ref "R43") (pin "1") (pinfunction "1_1") (pintype "passive"))
      (node (ref "U$2") (pin "P$6") (pinfunction "GPIO32_P$6") (pintype "bidirectional"))
    )
    (net (code "93") (name "Net-(U$2-GPIO33)") (class "Default")
      (node (ref "T16") (pin "B") (pinfunction "B_B") (pintype "passive"))
      (node (ref "U$2") (pin "P$5") (pinfunction "GPIO33_P$5") (pintype "bidirectional"))
    )
    (net (code "94") (name "Net-(U$3-PadF-)") (class "Default")
      (node (ref "U$3") (pin "F-") (pinfunction "F-_F-") (pintype "passive"))
      (node (ref "U$4") (pin "F+") (pinfunction "F+_F+") (pintype "passive"))
    )
    (net (code "95") (name "Net-(U$5-PadF-)") (class "Default")
      (node (ref "U$5") (pin "F-") (pinfunction "F-_F-") (pintype "passive"))
      (node (ref "U$6") (pin "F+") (pinfunction "F+_F+") (pintype "passive"))
    )
    (net (code "96") (name "Net-(U$7-PadF-)") (class "Default")
      (node (ref "U$7") (pin "F-") (pinfunction "F-_F-") (pintype "passive"))
      (node (ref "U$8") (pin "F+") (pinfunction "F+_F+") (pintype "passive"))
    )
    (net (code "97") (name "unconnected-(IC3B-SYNC-Pad2)") (class "Default")
      (node (ref "IC3") (pin "2") (pinfunction "SYNC_2") (pintype "input"))
    )
    (net (code "98") (name "unconnected-(IC3B-VREF-Pad6)") (class "Default")
      (node (ref "IC3") (pin "6") (pinfunction "VREF_6") (pintype "input"))
    )
    (net (code "99") (name "unconnected-(IC6-DOUT-Pad2)") (class "Default")
      (node (ref "IC6") (pin "2") (pinfunction "DOUT_2") (pintype "output"))
    )
    (net (code "100") (name "unconnected-(IC6-OUT3-Pad23)") (class "Default")
      (node (ref "IC6") (pin "23") (pinfunction "OUT3_23") (pintype "output"))
    )
    (net (code "101") (name "unconnected-(IC6-OUT4-Pad22)") (class "Default")
      (node (ref "IC6") (pin "22") (pinfunction "OUT4_22") (pintype "output"))
    )
    (net (code "102") (name "unconnected-(IC6-OUT5-Pad21)") (class "Default")
      (node (ref "IC6") (pin "21") (pinfunction "OUT5_21") (pintype "output"))
    )
    (net (code "103") (name "unconnected-(IC6-OUT6-Pad20)") (class "Default")
      (node (ref "IC6") (pin "20") (pinfunction "OUT6_20") (pintype "output"))
    )
    (net (code "104") (name "unconnected-(LED6-DO-Pad2-DOUT)") (class "Default")
      (node (ref "LED6") (pin "2-DOUT") (pinfunction "DO_2-DOUT") (pintype "output"))
    )
    (net (code "105") (name "unconnected-(SZA-S-PadP$1)") (class "Default")
      (node (ref "SZ") (pin "P$1") (pinfunction "S_P$1") (pintype "passive"))
    )
    (net (code "106") (name "unconnected-(SZC-S-PadP$2)") (class "Default")
      (node (ref "SZ") (pin "P$2") (pinfunction "S_P$2") (pintype "passive"))
    )
    (net (code "107") (name "unconnected-(U$1-CTS-Pad9)") (class "Default")
      (node (ref "U$1") (pin "9") (pinfunction "CTS_9") (pintype "bidirectional"))
    )
    (net (code "108") (name "unconnected-(U$1-DCD-Pad12)") (class "Default")
      (node (ref "U$1") (pin "12") (pinfunction "DCD_12") (pintype "bidirectional"))
    )
    (net (code "109") (name "unconnected-(U$1-DSR-Pad10)") (class "Default")
      (node (ref "U$1") (pin "10") (pinfunction "DSR_10") (pintype "bidirectional"))
    )
    (net (code "110") (name "unconnected-(U$1-RI-Pad11)") (class "Default")
      (node (ref "U$1") (pin "11") (pinfunction "RI_11") (pintype "bidirectional"))
    )
    (net (code "111") (name "unconnected-(U$1-RS232-Pad15)") (class "Default")
      (node (ref "U$1") (pin "15") (pinfunction "RS232_15") (pintype "bidirectional"))
    )
    (net (code "112") (name "unconnected-(U$1-RX-Pad3)") (class "Default")
      (node (ref "U$1") (pin "3") (pinfunction "RX_3") (pintype "bidirectional"))
    )
    (net (code "113") (name "unconnected-(U$1-TX-Pad2)") (class "Default")
      (node (ref "U$1") (pin "2") (pinfunction "TX_2") (pintype "bidirectional"))
    )
    (net (code "114") (name "unconnected-(U$1-V3-Pad4)") (class "Default")
      (node (ref "U$1") (pin "4") (pinfunction "V3_4") (pintype "bidirectional"))
    )
    (net (code "115") (name "unconnected-(U$2-CLK-PadP$15)") (class "Default")
      (node (ref "U$2") (pin "P$15") (pinfunction "CLK_P$15") (pintype "bidirectional"))
    )
    (net (code "116") (name "unconnected-(U$2-CMD-PadP$16)") (class "Default")
      (node (ref "U$2") (pin "P$16") (pinfunction "CMD_P$16") (pintype "bidirectional"))
    )
    (net (code "117") (name "unconnected-(U$2-GPIO34-PadP$4)") (class "Default")
      (node (ref "U$2") (pin "P$4") (pinfunction "GPIO34_P$4") (pintype "bidirectional"))
    )
    (net (code "118") (name "unconnected-(U$2-GPIO35-PadP$3)") (class "Default")
      (node (ref "U$2") (pin "P$3") (pinfunction "GPIO35_P$3") (pintype "bidirectional"))
    )
    (net (code "119") (name "unconnected-(U$2-SD0-PadP$18)") (class "Default")
      (node (ref "U$2") (pin "P$18") (pinfunction "SD0_P$18") (pintype "bidirectional"))
    )
    (net (code "120") (name "unconnected-(U$2-SD1-PadP$17)") (class "Default")
      (node (ref "U$2") (pin "P$17") (pinfunction "SD1_P$17") (pintype "bidirectional"))
    )
    (net (code "121") (name "unconnected-(U$2-SD2-PadP$14)") (class "Default")
      (node (ref "U$2") (pin "P$14") (pinfunction "SD2_P$14") (pintype "bidirectional"))
    )
    (net (code "122") (name "unconnected-(U$2-SD3-PadP$13)") (class "Default")
      (node (ref "U$2") (pin "P$13") (pinfunction "SD3_P$13") (pintype "bidirectional"))
    )
    (net (code "123") (name "unconnected-(X1-Pad4)") (class "Default")
      (node (ref "X1") (pin "4") (pinfunction "4_4") (pintype "passive"))
    )
  )
)
